# Baseboard_Main.net
KiCad netlist of a schematic drawn in EAGLE
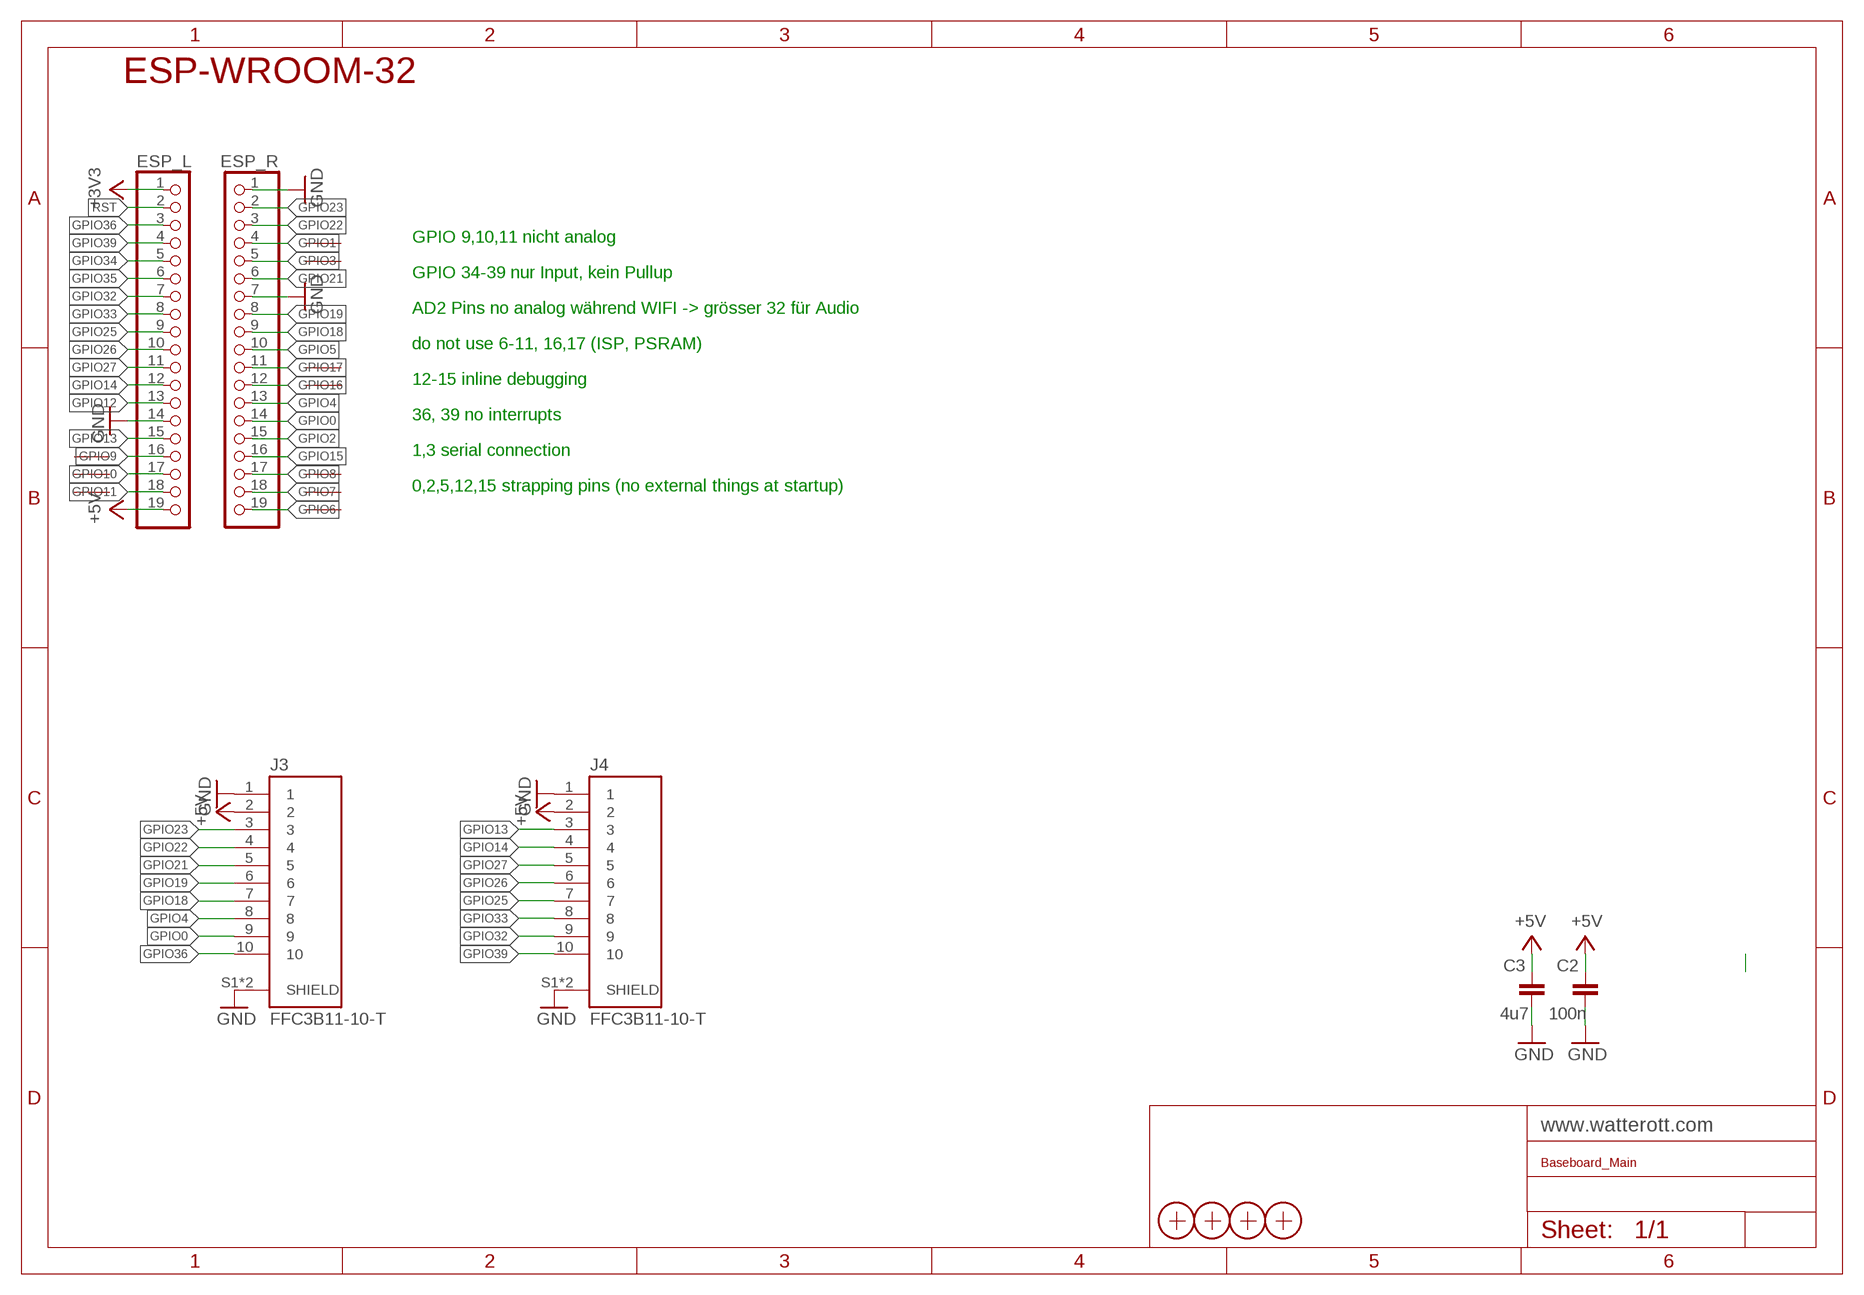
[diagram p0: schematic, sheet 1]

(export (version "E")
  (design (tool "Eeschema 10.0.6"))
  (components
    (comp (ref "C2")
      (value "100n")
      (footprint "eagle-import:C0805")
      (libsource (lib "eagle-import") (part "CAPACITOR-0805"))
    )
    (comp (ref "C3")
      (value "4u7")
      (footprint "eagle-import:C0805")
      (libsource (lib "eagle-import") (part "CAPACITOR-0805"))
    )
    (comp (ref "ESP_L")
      (value "PINHD-1X19")
      (footprint "eagle-import:1X19")
      (libsource (lib "eagle-import") (part "PINHD-1X19"))
    )
    (comp (ref "ESP_R")
      (value "PINHD-1X19")
      (footprint "eagle-import:1X19")
      (libsource (lib "eagle-import") (part "PINHD-1X19"))
    )
    (comp (ref "J3")
      (value "FFC3B11-10-T")
      (footprint "eagle-import:GCT_FFC3B11-10-T")
      (fields (field (name "MF") "Global Connector Technology"))
      (libsource (lib "eagle-import") (part "FFC3B11-10-T"))
    )
    (comp (ref "J4")
      (value "FFC3B11-10-T")
      (footprint "eagle-import:GCT_FFC3B11-10-T")
      (fields (field (name "MF") "Global Connector Technology"))
      (libsource (lib "eagle-import") (part "FFC3B11-10-T"))
    )
    (comp (ref "X1")
      (value "PASSER-07")
      (footprint "eagle-import:PASSER_07MM")
      (libsource (lib "eagle-import") (part "PASSER-07"))
    )
    (comp (ref "X2")
      (value "PASSER-07")
      (footprint "eagle-import:PASSER_07MM")
      (libsource (lib "eagle-import") (part "PASSER-07"))
    )
    (comp (ref "X3")
      (value "PASSER-07")
      (footprint "eagle-import:PASSER_07MM")
      (libsource (lib "eagle-import") (part "PASSER-07"))
    )
    (comp (ref "X4")
      (value "PASSER-07")
      (footprint "eagle-import:PASSER_07MM")
      (libsource (lib "eagle-import") (part "PASSER-07"))
    )
  )
  (nets
    (net (code "1") (name "+3V3") (class "Default")
      (node (ref "ESP_L") (pin "1") (pinfunction "1_1") (pintype "passive"))
    )
    (net (code "2") (name "+5V") (class "Default")
      (node (ref "C2") (pin "2") (pinfunction "2_2") (pintype "passive"))
      (node (ref "C3") (pin "2") (pinfunction "2_2") (pintype "passive"))
      (node (ref "ESP_L") (pin "19") (pinfunction "19_19") (pintype "passive"))
      (node (ref "J3") (pin "2") (pinfunction "2_2") (pintype "passive"))
      (node (ref "J4") (pin "2") (pinfunction "2_2") (pintype "passive"))
    )
    (net (code "3") (name "GND") (class "Default")
      (node (ref "C2") (pin "1") (pinfunction "1_1") (pintype "passive"))
      (node (ref "C3") (pin "1") (pinfunction "1_1") (pintype "passive"))
      (node (ref "ESP_L") (pin "14") (pinfunction "14_14") (pintype "passive"))
      (node (ref "ESP_R") (pin "1") (pinfunction "1_1") (pintype "passive"))
      (node (ref "ESP_R") (pin "7") (pinfunction "7_7") (pintype "passive"))
      (node (ref "J3") (pin "1") (pinfunction "1_1") (pintype "passive"))
      (node (ref "J3") (pin "S1") (pinfunction "SHIELD_S1") (pintype "passive"))
      (node (ref "J3") (pin "S2") (pinfunction "SHIELD_S2") (pintype "passive"))
      (node (ref "J4") (pin "1") (pinfunction "1_1") (pintype "passive"))
      (node (ref "J4") (pin "S1") (pinfunction "SHIELD_S1") (pintype "passive"))
      (node (ref "J4") (pin "S2") (pinfunction "SHIELD_S2") (pintype "passive"))
    )
    (net (code "4") (name "GPIO0") (class "Default")
      (node (ref "ESP_R") (pin "14") (pinfunction "14_14") (pintype "passive"))
      (node (ref "J3") (pin "9") (pinfunction "9_9") (pintype "passive"))
    )
    (net (code "5") (name "GPIO1") (class "Default")
      (node (ref "ESP_R") (pin "4") (pinfunction "4_4") (pintype "passive"))
    )
    (net (code "6") (name "GPIO2") (class "Default")
      (node (ref "ESP_R") (pin "15") (pinfunction "15_15") (pintype "passive"))
    )
    (net (code "7") (name "GPIO3") (class "Default")
      (node (ref "ESP_R") (pin "5") (pinfunction "5_5") (pintype "passive"))
    )
    (net (code "8") (name "GPIO4") (class "Default")
      (node (ref "ESP_R") (pin "13") (pinfunction "13_13") (pintype "passive"))
      (node (ref "J3") (pin "8") (pinfunction "8_8") (pintype "passive"))
    )
    (net (code "9") (name "GPIO5") (class "Default")
      (node (ref "ESP_R") (pin "10") (pinfunction "10_10") (pintype "passive"))
    )
    (net (code "10") (name "GPIO6") (class "Default")
      (node (ref "ESP_R") (pin "19") (pinfunction "19_19") (pintype "passive"))
    )
    (net (code "11") (name "GPIO7") (class "Default")
      (node (ref "ESP_R") (pin "18") (pinfunction "18_18") (pintype "passive"))
    )
    (net (code "12") (name "GPIO8") (class "Default")
      (node (ref "ESP_R") (pin "17") (pinfunction "17_17") (pintype "passive"))
    )
    (net (code "13") (name "GPIO9") (class "Default")
      (node (ref "ESP_L") (pin "16") (pinfunction "16_16") (pintype "passive"))
    )
    (net (code "14") (name "GPIO10") (class "Default")
      (node (ref "ESP_L") (pin "17") (pinfunction "17_17") (pintype "passive"))
    )
    (net (code "15") (name "GPIO11") (class "Default")
      (node (ref "ESP_L") (pin "18") (pinfunction "18_18") (pintype "passive"))
    )
    (net (code "16") (name "GPIO12") (class "Default")
      (node (ref "ESP_L") (pin "13") (pinfunction "13_13") (pintype "passive"))
    )
    (net (code "17") (name "GPIO13") (class "Default")
      (node (ref "ESP_L") (pin "15") (pinfunction "15_15") (pintype "passive"))
      (node (ref "J4") (pin "3") (pinfunction "3_3") (pintype "passive"))
    )
    (net (code "18") (name "GPIO14") (class "Default")
      (node (ref "ESP_L") (pin "12") (pinfunction "12_12") (pintype "passive"))
      (node (ref "J4") (pin "4") (pinfunction "4_4") (pintype "passive"))
    )
    (net (code "19") (name "GPIO15") (class "Default")
      (node (ref "ESP_R") (pin "16") (pinfunction "16_16") (pintype "passive"))
    )
    (net (code "20") (name "GPIO16") (class "Default")
      (node (ref "ESP_R") (pin "12") (pinfunction "12_12") (pintype "passive"))
    )
    (net (code "21") (name "GPIO17") (class "Default")
      (node (ref "ESP_R") (pin "11") (pinfunction "11_11") (pintype "passive"))
    )
    (net (code "22") (name "GPIO18") (class "Default")
      (node (ref "ESP_R") (pin "9") (pinfunction "9_9") (pintype "passive"))
      (node (ref "J3") (pin "7") (pinfunction "7_7") (pintype "passive"))
    )
    (net (code "23") (name "GPIO19") (class "Default")
      (node (ref "ESP_R") (pin "8") (pinfunction "8_8") (pintype "passive"))
      (node (ref "J3") (pin "6") (pinfunction "6_6") (pintype "passive"))
    )
    (net (code "24") (name "GPIO21") (class "Default")
      (node (ref "ESP_R") (pin "6") (pinfunction "6_6") (pintype "passive"))
      (node (ref "J3") (pin "5") (pinfunction "5_5") (pintype "passive"))
    )
    (net (code "25") (name "GPIO22") (class "Default")
      (node (ref "ESP_R") (pin "3") (pinfunction "3_3") (pintype "passive"))
      (node (ref "J3") (pin "4") (pinfunction "4_4") (pintype "passive"))
    )
    (net (code "26") (name "GPIO23") (class "Default")
      (node (ref "ESP_R") (pin "2") (pinfunction "2_2") (pintype "passive"))
      (node (ref "J3") (pin "3") (pinfunction "3_3") (pintype "passive"))
    )
    (net (code "27") (name "GPIO25") (class "Default")
      (node (ref "ESP_L") (pin "9") (pinfunction "9_9") (pintype "passive"))
      (node (ref "J4") (pin "7") (pinfunction "7_7") (pintype "passive"))
    )
    (net (code "28") (name "GPIO26") (class "Default")
      (node (ref "ESP_L") (pin "10") (pinfunction "10_10") (pintype "passive"))
      (node (ref "J4") (pin "6") (pinfunction "6_6") (pintype "passive"))
    )
    (net (code "29") (name "GPIO27") (class "Default")
      (node (ref "ESP_L") (pin "11") (pinfunction "11_11") (pintype "passive"))
      (node (ref "J4") (pin "5") (pinfunction "5_5") (pintype "passive"))
    )
    (net (code "30") (name "GPIO32") (class "Default")
      (node (ref "ESP_L") (pin "7") (pinfunction "7_7") (pintype "passive"))
      (node (ref "J4") (pin "9") (pinfunction "9_9") (pintype "passive"))
    )
    (net (code "31") (name "GPIO33") (class "Default")
      (node (ref "ESP_L") (pin "8") (pinfunction "8_8") (pintype "passive"))
      (node (ref "J4") (pin "8") (pinfunction "8_8") (pintype "passive"))
    )
    (net (code "32") (name "GPIO34") (class "Default")
      (node (ref "ESP_L") (pin "5") (pinfunction "5_5") (pintype "passive"))
    )
    (net (code "33") (name "GPIO35") (class "Default")
      (node (ref "ESP_L") (pin "6") (pinfunction "6_6") (pintype "passive"))
    )
    (net (code "34") (name "GPIO36") (class "Default")
      (node (ref "ESP_L") (pin "3") (pinfunction "3_3") (pintype "passive"))
      (node (ref "J3") (pin "10") (pinfunction "10_10") (pintype "passive"))
    )
    (net (code "35") (name "GPIO39") (class "Default")
      (node (ref "ESP_L") (pin "4") (pinfunction "4_4") (pintype "passive"))
      (node (ref "J4") (pin "10") (pinfunction "10_10") (pintype "passive"))
    )
    (net (code "36") (name "RST") (class "Default")
      (node (ref "ESP_L") (pin "2") (pinfunction "2_2") (pintype "passive"))
    )
  )
)
